# battery.net
KiCad netlist of a schematic drawn in Altium Designer
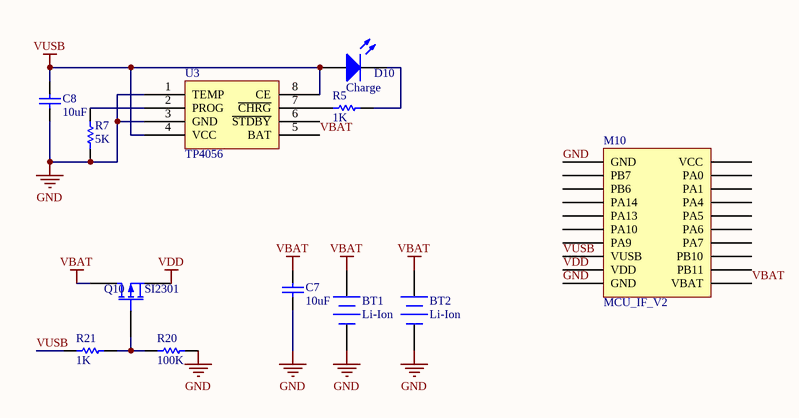
[diagram p0: battery.SchDoc]

(export (version "E")
  (design (tool "Eeschema 10.0.6"))
  (components
    (comp (ref "BT1")
      (value "Li-Ion")
      (footprint "HDR1X2H")
      (description "Multicell Battery")
      (fields (field (name "PUBLISHER") "Altium Limited"))
      (libsource (lib "Miscellaneous Devices") (part "Battery"))
    )
    (comp (ref "BT2")
      (value "Li-Ion")
      (footprint "Hearder2 2")
      (description "Multicell Battery")
      (fields (field (name "PUBLISHER") "Altium Limited"))
      (libsource (lib "Miscellaneous Devices") (part "Battery"))
    )
    (comp (ref "C7")
      (value "10uF")
      (footprint "C-1608[0603]")
      (description "Capacitor (Semiconductor SIM Model)")
      (fields (field (name "Comment") "Cap Semi") (field (name "PUBLISHER") "Altium Limited"))
      (libsource (lib "Miscellaneous Devices") (part "Cap Semi"))
    )
    (comp (ref "C8")
      (value "10uF")
      (footprint "C-1608[0603]")
      (description "Capacitor (Semiconductor SIM Model)")
      (fields (field (name "Comment") "Cap Semi") (field (name "PUBLISHER") "Altium Limited"))
      (libsource (lib "Miscellaneous Devices") (part "Cap Semi"))
    )
    (comp (ref "D10")
      (value "Charge")
      (footprint "LED-1608[0603]-R")
      (description "Typical RED, GREEN, YELLOW, AMBER GaAs LED")
      (fields (field (name "PUBLISHER") "Altium Limited"))
      (libsource (lib "Miscellaneous Devices") (part "LED2"))
    )
    (comp (ref "M10")
      (value "MCU_IF_V2")
      (footprint "MCU_IF_V2")
      (libsource (lib "MCU_IF") (part "MCU_IF_V1"))
    )
    (comp (ref "Q10")
      (value "SI2301")
      (footprint "SOT23B")
      (description "P-Channel MOSFET")
      (fields (field (name "PUBLISHER") "Altium Limited"))
      (libsource (lib "Miscellaneous Devices") (part "MOSFET-P"))
    )
    (comp (ref "R5")
      (value "1K")
      (footprint "R-1608[0603]")
      (description "Semiconductor Resistor")
      (fields (field (name "Comment") "Res Semi") (field (name "PUBLISHER") "Altium Limited"))
      (libsource (lib "Miscellaneous Devices") (part "Res Semi"))
    )
    (comp (ref "R7")
      (value "5K")
      (footprint "R-1608[0603]")
      (description "Semiconductor Resistor")
      (fields (field (name "Comment") "Res Semi") (field (name "PUBLISHER") "Altium Limited"))
      (libsource (lib "Miscellaneous Devices") (part "Res Semi"))
    )
    (comp (ref "R20")
      (value "100K")
      (footprint "R-1608[0603]")
      (description "Semiconductor Resistor")
      (fields (field (name "Comment") "Res Semi") (field (name "PUBLISHER") "Altium Limited"))
      (libsource (lib "Miscellaneous Devices") (part "Res Semi"))
    )
    (comp (ref "R21")
      (value "1K")
      (footprint "R-1608[0603]")
      (description "Semiconductor Resistor")
      (fields (field (name "Comment") "Res Semi") (field (name "PUBLISHER") "Altium Limited"))
      (libsource (lib "Miscellaneous Devices") (part "Res Semi"))
    )
    (comp (ref "U3") (value "TP4056") (footprint "TP4056") (libsource (lib "Schlib1") (part "TP4056")))
  )
  (nets
    (net (code "1") (name "GND") (class "Default")
      (node (ref "BT1") (pin "2") (pinfunction "-_2") (pintype "passive"))
      (node (ref "BT2") (pin "2") (pinfunction "-_2") (pintype "passive"))
      (node (ref "C7") (pin "1") (pinfunction "1_1") (pintype "passive"))
      (node (ref "C8") (pin "1") (pinfunction "1_1") (pintype "passive"))
      (node (ref "M10") (pin "1") (pinfunction "GND_1") (pintype "passive"))
      (node (ref "M10") (pin "10") (pinfunction "GND_10") (pintype "passive"))
      (node (ref "R20") (pin "2") (pinfunction "2_2") (pintype "passive"))
      (node (ref "R7") (pin "1") (pinfunction "1_1") (pintype "passive"))
      (node (ref "U3") (pin "1") (pinfunction "TEMP_1") (pintype "passive"))
      (node (ref "U3") (pin "3") (pinfunction "GND_3") (pintype "passive"))
    )
    (net (code "2") (name "Net-(D10-K)") (class "Default")
      (node (ref "D10") (pin "2") (pinfunction "K_2") (pintype "passive"))
      (node (ref "R5") (pin "1") (pinfunction "1_1") (pintype "passive"))
    )
    (net (code "3") (name "Net-(Q10-G)") (class "Default")
      (node (ref "Q10") (pin "2") (pinfunction "G_2") (pintype "passive"))
      (node (ref "R20") (pin "1") (pinfunction "1_1") (pintype "passive"))
      (node (ref "R21") (pin "2") (pinfunction "2_2") (pintype "passive"))
    )
    (net (code "4") (name "Net-(U3-PROG)") (class "Default")
      (node (ref "R7") (pin "2") (pinfunction "2_2") (pintype "passive"))
      (node (ref "U3") (pin "2") (pinfunction "PROG_2") (pintype "passive"))
    )
    (net (code "5") (name "Net-(U3-~{CHRG})") (class "Default")
      (node (ref "R5") (pin "2") (pinfunction "2_2") (pintype "passive"))
      (node (ref "U3") (pin "7") (pinfunction "~{CHRG}_7") (pintype "passive"))
    )
    (net (code "6") (name "VBAT") (class "Default")
      (node (ref "BT1") (pin "1") (pinfunction "+_1") (pintype "passive"))
      (node (ref "BT2") (pin "1") (pinfunction "+_1") (pintype "passive"))
      (node (ref "C7") (pin "2") (pinfunction "2_2") (pintype "passive"))
      (node (ref "M10") (pin "11") (pinfunction "VBAT_11") (pintype "passive"))
      (node (ref "Q10") (pin "1") (pinfunction "D_1") (pintype "passive"))
      (node (ref "U3") (pin "5") (pinfunction "BAT_5") (pintype "passive"))
    )
    (net (code "7") (name "VDD") (class "Default")
      (node (ref "M10") (pin "9") (pinfunction "VDD_9") (pintype "passive"))
      (node (ref "Q10") (pin "3") (pinfunction "S_3") (pintype "passive"))
    )
    (net (code "8") (name "VUSB") (class "Default")
      (node (ref "C8") (pin "2") (pinfunction "2_2") (pintype "passive"))
      (node (ref "D10") (pin "1") (pinfunction "A_1") (pintype "passive"))
      (node (ref "M10") (pin "8") (pinfunction "VUSB_8") (pintype "passive"))
      (node (ref "R21") (pin "1") (pinfunction "1_1") (pintype "passive"))
      (node (ref "U3") (pin "4") (pinfunction "VCC_4") (pintype "passive"))
      (node (ref "U3") (pin "8") (pinfunction "CE_8") (pintype "passive"))
    )
    (net (code "9") (name "unconnected-(M10-PA0-Pad19)") (class "Default")
      (node (ref "M10") (pin "19") (pinfunction "PA0_19") (pintype "passive"))
    )
    (net (code "10") (name "unconnected-(M10-PA1-Pad18)") (class "Default")
      (node (ref "M10") (pin "18") (pinfunction "PA1_18") (pintype "passive"))
    )
    (net (code "11") (name "unconnected-(M10-PA4-Pad17)") (class "Default")
      (node (ref "M10") (pin "17") (pinfunction "PA4_17") (pintype "passive"))
    )
    (net (code "12") (name "unconnected-(M10-PA5-Pad16)") (class "Default")
      (node (ref "M10") (pin "16") (pinfunction "PA5_16") (pintype "passive"))
    )
    (net (code "13") (name "unconnected-(M10-PA6-Pad15)") (class "Default")
      (node (ref "M10") (pin "15") (pinfunction "PA6_15") (pintype "passive"))
    )
    (net (code "14") (name "unconnected-(M10-PA7-Pad14)") (class "Default")
      (node (ref "M10") (pin "14") (pinfunction "PA7_14") (pintype "passive"))
    )
    (net (code "15") (name "unconnected-(M10-PA9-Pad7)") (class "Default")
      (node (ref "M10") (pin "7") (pinfunction "PA9_7") (pintype "passive"))
    )
    (net (code "16") (name "unconnected-(M10-PA10-Pad6)") (class "Default")
      (node (ref "M10") (pin "6") (pinfunction "PA10_6") (pintype "passive"))
    )
    (net (code "17") (name "unconnected-(M10-PA13-Pad5)") (class "Default")
      (node (ref "M10") (pin "5") (pinfunction "PA13_5") (pintype "passive"))
    )
    (net (code "18") (name "unconnected-(M10-PA14-Pad4)") (class "Default")
      (node (ref "M10") (pin "4") (pinfunction "PA14_4") (pintype "passive"))
    )
    (net (code "19") (name "unconnected-(M10-PB6-Pad3)") (class "Default")
      (node (ref "M10") (pin "3") (pinfunction "PB6_3") (pintype "passive"))
    )
    (net (code "20") (name "unconnected-(M10-PB7-Pad2)") (class "Default")
      (node (ref "M10") (pin "2") (pinfunction "PB7_2") (pintype "passive"))
    )
    (net (code "21") (name "unconnected-(M10-PB10-Pad13)") (class "Default")
      (node (ref "M10") (pin "13") (pinfunction "PB10_13") (pintype "passive"))
    )
    (net (code "22") (name "unconnected-(M10-PB11-Pad12)") (class "Default")
      (node (ref "M10") (pin "12") (pinfunction "PB11_12") (pintype "passive"))
    )
    (net (code "23") (name "unconnected-(M10-VCC-Pad20)") (class "Default")
      (node (ref "M10") (pin "20") (pinfunction "VCC_20") (pintype "passive"))
    )
    (net (code "24") (name "unconnected-(U3-~{STDBY}-Pad6)") (class "Default")
      (node (ref "U3") (pin "6") (pinfunction "~{STDBY}_6") (pintype "passive"))
    )
  )
)
